# alt_rpd_schematic.net
KiCad netlist of a schematic drawn in EAGLE
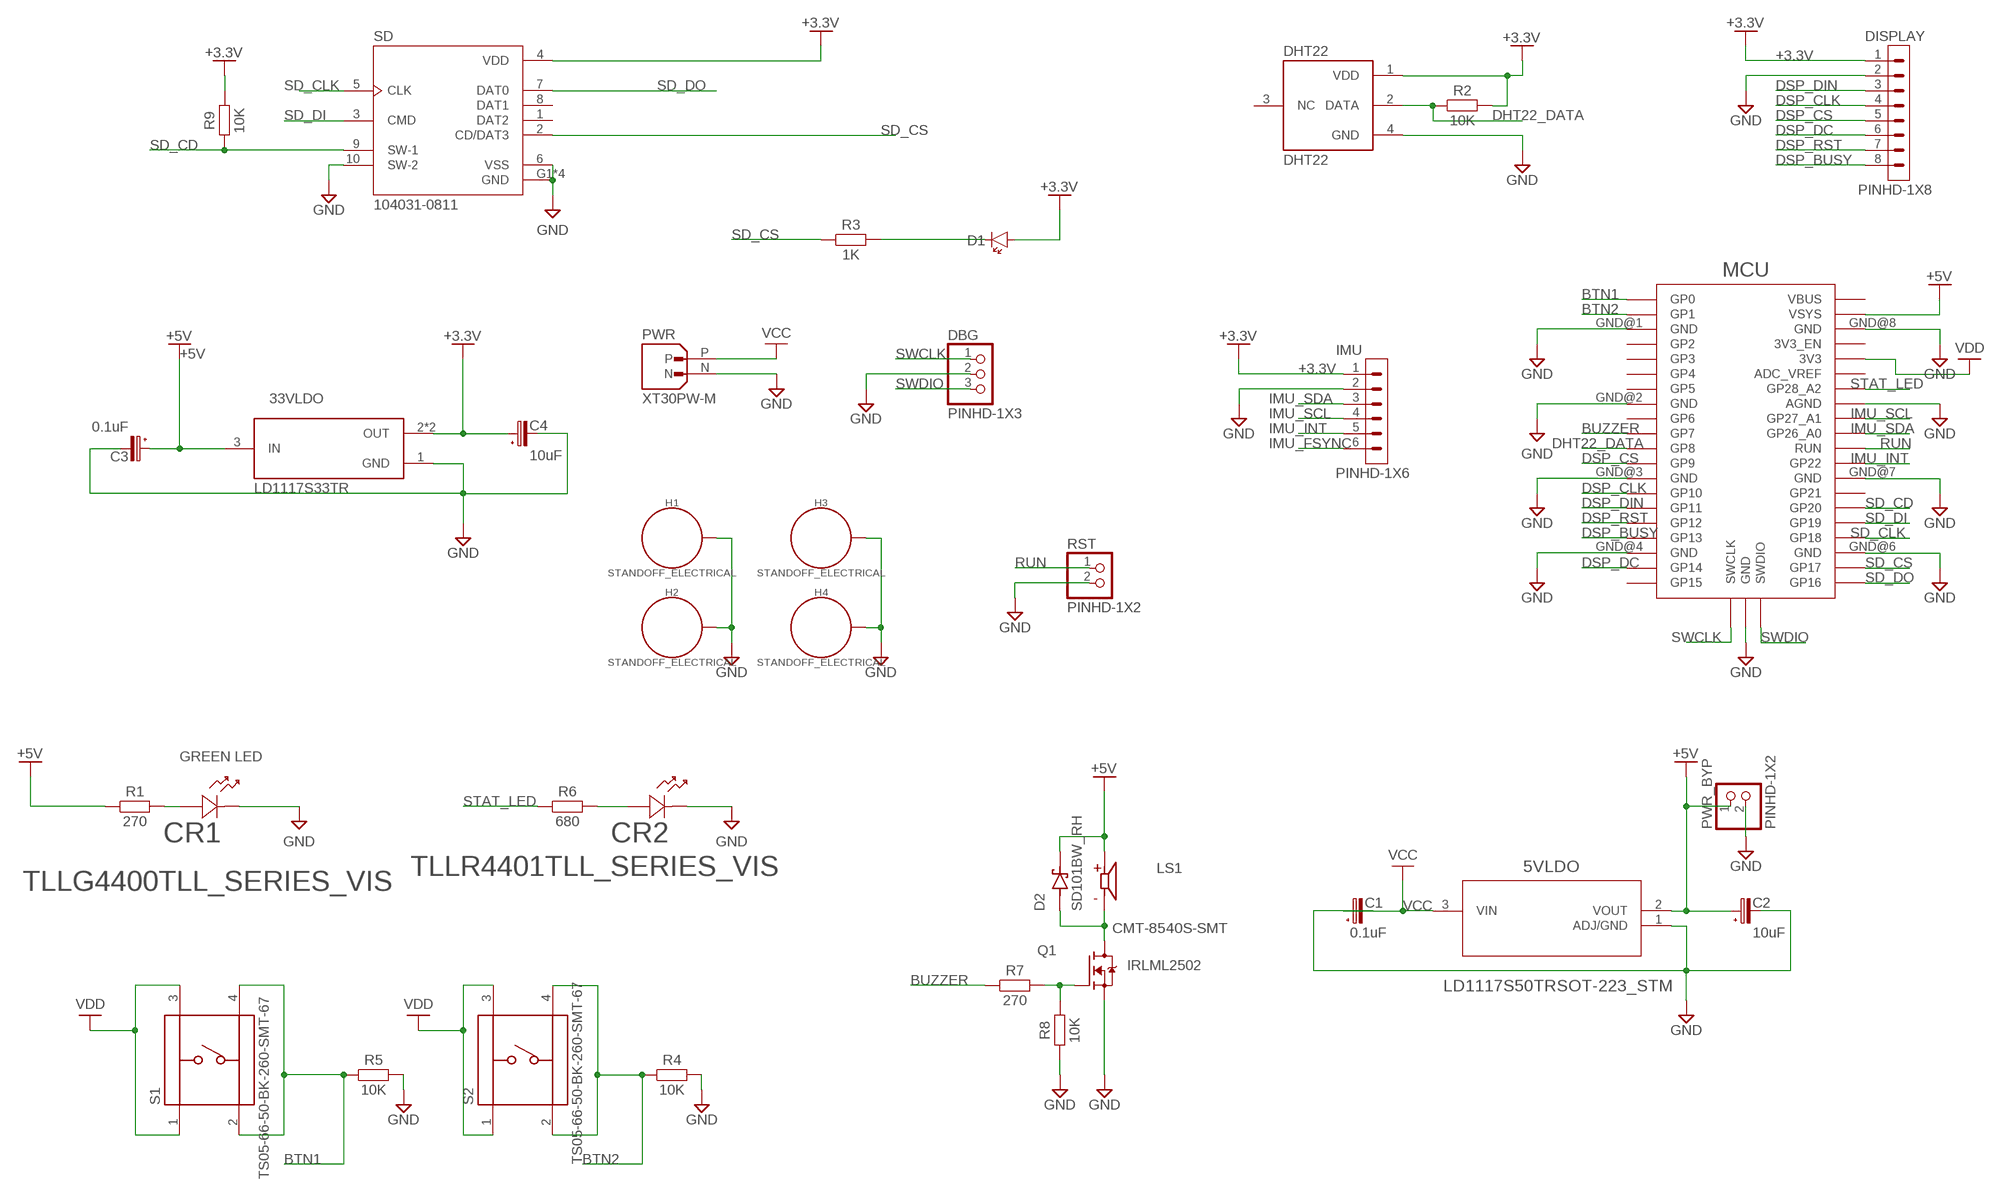
[diagram p0: schematic, sheet 1]

(export (version "E")
  (design (tool "Eeschema 10.0.6"))
  (components
    (comp (ref "5VLDO")
      (value "LD1117S50TRSOT-223_STM")
      (footprint "eagle-import:SOT-223_STM")
      (fields
        (field (name "MANUFACTURER_PART_NUMBER") "LD1117S50TR")
        (field (name "COPYRIGHT") "Copyright (C) 2026 Ultra Librarian. All rights reserved.")
      )
      (libsource (lib "eagle-import") (part "LD1117S50TRSOT-223_STM"))
    )
    (comp (ref "33VLDO")
      (value "LD1117S33TR")
      (footprint "eagle-import:SOT230P700X180-4N")
      (fields (field (name "MANUFACTURER") "ST Microelectronics"))
      (libsource (lib "eagle-import") (part "LD1117S33TR"))
    )
    (comp (ref "C1")
      (value "0.1uF")
      (footprint "eagle-import:CAPMP3216X180N")
      (libsource (lib "eagle-import") (part "C-POLTANTALUM-1206(3216-METRIC)_"))
    )
    (comp (ref "C2")
      (value "10uF")
      (footprint "eagle-import:CAPMP3216X180N")
      (libsource (lib "eagle-import") (part "C-POLTANTALUM-1206(3216-METRIC)_"))
    )
    (comp (ref "C3")
      (value "0.1uF")
      (footprint "eagle-import:CAPMP3216X180N")
      (libsource (lib "eagle-import") (part "C-POLTANTALUM-1206(3216-METRIC)_"))
    )
    (comp (ref "C4")
      (value "10uF")
      (footprint "eagle-import:CAPMP3216X180N")
      (libsource (lib "eagle-import") (part "C-POLTANTALUM-1206(3216-METRIC)_"))
    )
    (comp (ref "CR1")
      (value "TLLG4400TLL_SERIES_VIS")
      (footprint "eagle-import:TLL_SERIES_VIS")
      (description "GREEN LED")
      (fields
        (field (name "MANUFACTURER_PART_NUMBER") "TLLG4400")
        (field (name "COPYRIGHT") "Copyright (C) 2026 Ultra Librarian. All rights reserved.")
      )
      (libsource (lib "eagle-import") (part "TLLG4400TLL_SERIES_VIS"))
    )
    (comp (ref "CR2")
      (value "TLLR4401TLL_SERIES_VIS")
      (footprint "eagle-import:TLL_SERIES_VIS")
      (fields
        (field (name "MANUFACTURER_PART_NUMBER") "TLLR4401")
        (field (name "COPYRIGHT") "Copyright (C) 2026 Ultra Librarian. All rights reserved.")
      )
      (libsource (lib "eagle-import") (part "TLLR4401TLL_SERIES_VIS"))
    )
    (comp (ref "D1")
      (value "LED_RED")
      (footprint "eagle-import:LEDC2012X110N_FLAT-R")
      (libsource (lib "eagle-import") (part "CHIP-FLAT-R_0805"))
    )
    (comp (ref "D2")
      (value "SD101BW_RH")
      (footprint "eagle-import:DIO_SD101BW_RH")
      (fields (field (name "MF") "Taiwan Semiconductor") (field (name "MP") "BAT46GW RHG"))
      (libsource (lib "eagle-import") (part "SD101BW_RH"))
    )
    (comp (ref "DBG")
      (value "PINHD-1X3")
      (footprint "eagle-import:1X03")
      (libsource (lib "eagle-import") (part "PINHD-1X3"))
    )
    (comp (ref "DHT22")
      (value "DHT22")
      (footprint "eagle-import:XDCR_DHT22")
      (fields (field (name "MANUFACTURER") "Aosong Electronics") (field (name "CREATOR") "KARTHIK"))
      (libsource (lib "eagle-import") (part "DHT22"))
    )
    (comp (ref "DISPLAY")
      (value "PINHD-1X8")
      (footprint "eagle-import:1X08")
      (libsource (lib "eagle-import") (part "PINHD-1X8"))
    )
    (comp (ref "H1")
      (value "STANDOFF_ELECTRICAL")
      (footprint "eagle-import:STANDOFF-ELECTRICAL")
      (libsource (lib "eagle-import") (part "STANDOFF_ELECTRICAL"))
    )
    (comp (ref "H2")
      (value "STANDOFF_ELECTRICAL")
      (footprint "eagle-import:STANDOFF-ELECTRICAL")
      (libsource (lib "eagle-import") (part "STANDOFF_ELECTRICAL"))
    )
    (comp (ref "H3")
      (value "STANDOFF_ELECTRICAL")
      (footprint "eagle-import:STANDOFF-ELECTRICAL")
      (libsource (lib "eagle-import") (part "STANDOFF_ELECTRICAL"))
    )
    (comp (ref "H4")
      (value "STANDOFF_ELECTRICAL")
      (footprint "eagle-import:STANDOFF-ELECTRICAL")
      (libsource (lib "eagle-import") (part "STANDOFF_ELECTRICAL"))
    )
    (comp (ref "IMU")
      (value "PINHD-1X6")
      (footprint "eagle-import:1X06")
      (libsource (lib "eagle-import") (part "PINHD-1X6"))
    )
    (comp (ref "LS1")
      (value "CMT-8540S-SMT")
      (footprint "eagle-import:CUI_CMT-8540S-SMT")
      (fields (field (name "MF") "CUI"))
      (libsource (lib "eagle-import") (part "CMT-8540S-SMT"))
    )
    (comp (ref "MCU")
      (value "RPI_PICO_IG-SMD")
      (footprint "eagle-import:RPI_PICO")
      (libsource (lib "eagle-import") (part "RPI_PICO_IG-SMD"))
    )
    (comp (ref "PWR")
      (value "XT30PW-M")
      (footprint "eagle-import:AMASS_XT30PW-M")
      (fields (field (name "MANUFACTURER") "Amass"))
      (libsource (lib "eagle-import") (part "XT30PW-M"))
    )
    (comp (ref "PWR_BYP")
      (value "PINHD-1X2")
      (footprint "eagle-import:1X02")
      (libsource (lib "eagle-import") (part "PINHD-1X2"))
    )
    (comp (ref "Q1")
      (value "IRLML2502")
      (footprint "eagle-import:SOT95P237X112-3N")
      (fields (field (name "MANUFACTURER") "Infineon Technologies"))
      (libsource (lib "eagle-import") (part "IRLML2502"))
    )
    (comp (ref "R1")
      (value "270")
      (footprint "eagle-import:RESC3224X71")
      (libsource (lib "eagle-import") (part "RCHIP-1210(3225-METRIC)_"))
    )
    (comp (ref "R2")
      (value "10K")
      (footprint "eagle-import:RESC3216X70")
      (libsource (lib "eagle-import") (part "RCHIP-1206(3216-METRIC)_"))
    )
    (comp (ref "R3")
      (value "1K")
      (footprint "eagle-import:RESC3216X70")
      (libsource (lib "eagle-import") (part "RCHIP-1206(3216-METRIC)_"))
    )
    (comp (ref "R4")
      (value "10K")
      (footprint "eagle-import:RESC3216X70")
      (libsource (lib "eagle-import") (part "RCHIP-1206(3216-METRIC)_"))
    )
    (comp (ref "R5")
      (value "10K")
      (footprint "eagle-import:RESC3216X70")
      (libsource (lib "eagle-import") (part "RCHIP-1206(3216-METRIC)_"))
    )
    (comp (ref "R6")
      (value "680")
      (footprint "eagle-import:RESC3224X71")
      (libsource (lib "eagle-import") (part "RCHIP-1210(3225-METRIC)_"))
    )
    (comp (ref "R7")
      (value "270")
      (footprint "eagle-import:RESC3224X71")
      (libsource (lib "eagle-import") (part "RCHIP-1210(3225-METRIC)_"))
    )
    (comp (ref "R8")
      (value "10K")
      (footprint "eagle-import:RESC3216X70")
      (libsource (lib "eagle-import") (part "RCHIP-1206(3216-METRIC)_"))
    )
    (comp (ref "R9")
      (value "10K")
      (footprint "eagle-import:RESC3216X70")
      (libsource (lib "eagle-import") (part "RCHIP-1206(3216-METRIC)_"))
    )
    (comp (ref "RST")
      (value "PINHD-1X2")
      (footprint "eagle-import:1X02")
      (libsource (lib "eagle-import") (part "PINHD-1X2"))
    )
    (comp (ref "S1")
      (value "TS05-66-50-BK-260-SMT-67")
      (footprint "eagle-import:SW_TS05-66-50-BK-260-SMT-67")
      (fields (field (name "MANUFACTURER") "CUI Devices"))
      (libsource (lib "eagle-import") (part "TS05-66-50-BK-260-SMT-67"))
    )
    (comp (ref "S2")
      (value "TS05-66-50-BK-260-SMT-67")
      (footprint "eagle-import:SW_TS05-66-50-BK-260-SMT-67")
      (fields (field (name "MANUFACTURER") "CUI Devices"))
      (libsource (lib "eagle-import") (part "TS05-66-50-BK-260-SMT-67"))
    )
    (comp (ref "SD")
      (value "104031-0811")
      (footprint "eagle-import:MOLEX_104031-0811")
      (fields (field (name "MANUFACTURER") "Molex"))
      (libsource (lib "eagle-import") (part "104031-0811"))
    )
  )
  (nets
    (net (code "1") (name "+3.3V") (class "Default")
      (node (ref "33VLDO") (pin "2") (pinfunction "OUT_2") (pintype "output"))
      (node (ref "33VLDO") (pin "4") (pinfunction "OUT_4") (pintype "output"))
      (node (ref "C4") (pin "1") (pinfunction "+_1") (pintype "passive"))
      (node (ref "D1") (pin "A") (pinfunction "A_A") (pintype "passive"))
      (node (ref "DHT22") (pin "1") (pinfunction "VDD_1") (pintype "power_in"))
      (node (ref "DISPLAY") (pin "1") (pinfunction "1_1") (pintype "passive"))
      (node (ref "IMU") (pin "1") (pinfunction "1_1") (pintype "passive"))
      (node (ref "R2") (pin "2") (pinfunction "2_2") (pintype "passive"))
      (node (ref "R9") (pin "2") (pinfunction "2_2") (pintype "passive"))
      (node (ref "SD") (pin "4") (pinfunction "VDD_4") (pintype "power_in"))
    )
    (net (code "2") (name "+5V") (class "Default")
      (node (ref "33VLDO") (pin "3") (pinfunction "IN_3") (pintype "input"))
      (node (ref "5VLDO") (pin "2") (pinfunction "VOUT_2") (pintype "power_in"))
      (node (ref "C2") (pin "1") (pinfunction "+_1") (pintype "passive"))
      (node (ref "C3") (pin "1") (pinfunction "+_1") (pintype "passive"))
      (node (ref "D2") (pin "C") (pinfunction "K_C") (pintype "passive"))
      (node (ref "LS1") (pin "P") (pinfunction "P_P") (pintype "passive"))
      (node (ref "MCU") (pin "VSYS") (pinfunction "VSYS_VSYS") (pintype "bidirectional"))
      (node (ref "PWR_BYP") (pin "1") (pinfunction "1_1") (pintype "passive"))
      (node (ref "R1") (pin "1") (pinfunction "1_1") (pintype "passive"))
    )
    (net (code "3") (name "/BTN1") (class "Default")
      (node (ref "MCU") (pin "GP0") (pinfunction "GP0_GP0") (pintype "bidirectional"))
      (node (ref "R5") (pin "1") (pinfunction "1_1") (pintype "passive"))
      (node (ref "S1") (pin "2") (pinfunction "2_2") (pintype "passive"))
      (node (ref "S1") (pin "4") (pinfunction "4_4") (pintype "passive"))
    )
    (net (code "4") (name "/BTN2") (class "Default")
      (node (ref "MCU") (pin "GP1") (pinfunction "GP1_GP1") (pintype "bidirectional"))
      (node (ref "R4") (pin "1") (pinfunction "1_1") (pintype "passive"))
      (node (ref "S2") (pin "2") (pinfunction "2_2") (pintype "passive"))
      (node (ref "S2") (pin "4") (pinfunction "4_4") (pintype "passive"))
    )
    (net (code "5") (name "/BUZZER") (class "Default")
      (node (ref "MCU") (pin "GP7") (pinfunction "GP7_GP7") (pintype "bidirectional"))
      (node (ref "R7") (pin "1") (pinfunction "1_1") (pintype "passive"))
    )
    (net (code "6") (name "/DHT22_DATA") (class "Default")
      (node (ref "DHT22") (pin "2") (pinfunction "DATA_2") (pintype "bidirectional"))
      (node (ref "MCU") (pin "GP8") (pinfunction "GP8_GP8") (pintype "bidirectional"))
      (node (ref "R2") (pin "1") (pinfunction "1_1") (pintype "passive"))
    )
    (net (code "7") (name "/DSP_BUSY") (class "Default")
      (node (ref "DISPLAY") (pin "8") (pinfunction "8_8") (pintype "passive"))
      (node (ref "MCU") (pin "GP13") (pinfunction "GP13_GP13") (pintype "bidirectional"))
    )
    (net (code "8") (name "/DSP_CLK") (class "Default")
      (node (ref "DISPLAY") (pin "4") (pinfunction "4_4") (pintype "passive"))
      (node (ref "MCU") (pin "GP10") (pinfunction "GP10_GP10") (pintype "bidirectional"))
    )
    (net (code "9") (name "/DSP_CS") (class "Default")
      (node (ref "DISPLAY") (pin "5") (pinfunction "5_5") (pintype "passive"))
      (node (ref "MCU") (pin "GP9") (pinfunction "GP9_GP9") (pintype "bidirectional"))
    )
    (net (code "10") (name "/DSP_DC") (class "Default")
      (node (ref "DISPLAY") (pin "6") (pinfunction "6_6") (pintype "passive"))
      (node (ref "MCU") (pin "GP14") (pinfunction "GP14_GP14") (pintype "bidirectional"))
    )
    (net (code "11") (name "/DSP_DIN") (class "Default")
      (node (ref "DISPLAY") (pin "3") (pinfunction "3_3") (pintype "passive"))
      (node (ref "MCU") (pin "GP11") (pinfunction "GP11_GP11") (pintype "bidirectional"))
    )
    (net (code "12") (name "/DSP_RST") (class "Default")
      (node (ref "DISPLAY") (pin "7") (pinfunction "7_7") (pintype "passive"))
      (node (ref "MCU") (pin "GP12") (pinfunction "GP12_GP12") (pintype "bidirectional"))
    )
    (net (code "13") (name "/IMU_FSYNC") (class "Default")
      (node (ref "IMU") (pin "6") (pinfunction "6_6") (pintype "passive"))
    )
    (net (code "14") (name "/IMU_INT") (class "Default")
      (node (ref "IMU") (pin "5") (pinfunction "5_5") (pintype "passive"))
      (node (ref "MCU") (pin "GP22") (pinfunction "GP22_GP22") (pintype "bidirectional"))
    )
    (net (code "15") (name "/IMU_SCL") (class "Default")
      (node (ref "IMU") (pin "4") (pinfunction "4_4") (pintype "passive"))
      (node (ref "MCU") (pin "GP27_A1") (pinfunction "GP27_A1_GP27_A1") (pintype "bidirectional"))
    )
    (net (code "16") (name "/IMU_SDA") (class "Default")
      (node (ref "IMU") (pin "3") (pinfunction "3_3") (pintype "passive"))
      (node (ref "MCU") (pin "GP26_A0") (pinfunction "GP26_A0_GP26_A0") (pintype "bidirectional"))
    )
    (net (code "17") (name "/RUN") (class "Default")
      (node (ref "MCU") (pin "RUN") (pinfunction "RUN_RUN") (pintype "bidirectional"))
      (node (ref "RST") (pin "1") (pinfunction "1_1") (pintype "passive"))
    )
    (net (code "18") (name "/SD_CD") (class "Default")
      (node (ref "MCU") (pin "GP20") (pinfunction "GP20_GP20") (pintype "bidirectional"))
      (node (ref "R9") (pin "1") (pinfunction "1_1") (pintype "passive"))
      (node (ref "SD") (pin "9") (pinfunction "SW-1_9") (pintype "passive"))
    )
    (net (code "19") (name "/SD_CLK") (class "Default")
      (node (ref "MCU") (pin "GP18") (pinfunction "GP18_GP18") (pintype "bidirectional"))
      (node (ref "SD") (pin "5") (pinfunction "CLK_5") (pintype "input"))
    )
    (net (code "20") (name "/SD_CS") (class "Default")
      (node (ref "MCU") (pin "GP17") (pinfunction "GP17_GP17") (pintype "bidirectional"))
      (node (ref "R3") (pin "1") (pinfunction "1_1") (pintype "passive"))
      (node (ref "SD") (pin "2") (pinfunction "CD/DAT3_2") (pintype "bidirectional"))
    )
    (net (code "21") (name "/SD_DI") (class "Default")
      (node (ref "MCU") (pin "GP19") (pinfunction "GP19_GP19") (pintype "bidirectional"))
      (node (ref "SD") (pin "3") (pinfunction "CMD_3") (pintype "bidirectional"))
    )
    (net (code "22") (name "/SD_DO") (class "Default")
      (node (ref "MCU") (pin "GP16") (pinfunction "GP16_GP16") (pintype "bidirectional"))
      (node (ref "SD") (pin "7") (pinfunction "DAT0_7") (pintype "bidirectional"))
    )
    (net (code "23") (name "/STAT_LED") (class "Default")
      (node (ref "MCU") (pin "GP28_A2") (pinfunction "GP28_A2_GP28_A2") (pintype "bidirectional"))
      (node (ref "R6") (pin "1") (pinfunction "1_1") (pintype "passive"))
    )
    (net (code "24") (name "/SWCLK") (class "Default")
      (node (ref "DBG") (pin "1") (pinfunction "1_1") (pintype "passive"))
      (node (ref "MCU") (pin "SWCLK") (pinfunction "SWCLK_SWCLK") (pintype "bidirectional"))
    )
    (net (code "25") (name "/SWDIO") (class "Default")
      (node (ref "DBG") (pin "3") (pinfunction "3_3") (pintype "passive"))
      (node (ref "MCU") (pin "SWDIO") (pinfunction "SWDIO_SWDIO") (pintype "bidirectional"))
    )
    (net (code "26") (name "GND") (class "Default")
      (node (ref "33VLDO") (pin "1") (pinfunction "GND_1") (pintype "power_in"))
      (node (ref "5VLDO") (pin "1") (pinfunction "ADJ/GND_1") (pintype "passive"))
      (node (ref "C1") (pin "2") (pinfunction "-_2") (pintype "passive"))
      (node (ref "C2") (pin "2") (pinfunction "-_2") (pintype "passive"))
      (node (ref "C3") (pin "2") (pinfunction "-_2") (pintype "passive"))
      (node (ref "C4") (pin "2") (pinfunction "-_2") (pintype "passive"))
      (node (ref "CR1") (pin "1") (pinfunction "1_1") (pintype "passive"))
      (node (ref "CR2") (pin "1") (pinfunction "1_1") (pintype "passive"))
      (node (ref "DBG") (pin "2") (pinfunction "2_2") (pintype "passive"))
      (node (ref "DHT22") (pin "4") (pinfunction "GND_4") (pintype "power_in"))
      (node (ref "DISPLAY") (pin "2") (pinfunction "2_2") (pintype "passive"))
      (node (ref "H1") (pin "P1") (pinfunction "P$1_P1") (pintype "bidirectional"))
      (node (ref "H2") (pin "P1") (pinfunction "P$1_P1") (pintype "bidirectional"))
      (node (ref "H3") (pin "P1") (pinfunction "P$1_P1") (pintype "bidirectional"))
      (node (ref "H4") (pin "P1") (pinfunction "P$1_P1") (pintype "bidirectional"))
      (node (ref "IMU") (pin "2") (pinfunction "2_2") (pintype "passive"))
      (node (ref "MCU") (pin "AGND") (pinfunction "AGND_AGND") (pintype "bidirectional"))
      (node (ref "MCU") (pin "GND@1") (pinfunction "GND_GND@1") (pintype "bidirectional"))
      (node (ref "MCU") (pin "GND@2") (pinfunction "GND_GND@2") (pintype "bidirectional"))
      (node (ref "MCU") (pin "GND@3") (pinfunction "GND_GND@3") (pintype "bidirectional"))
      (node (ref "MCU") (pin "GND@4") (pinfunction "GND_GND@4") (pintype "bidirectional"))
      (node (ref "MCU") (pin "GND@5") (pinfunction "GND_GND@5") (pintype "bidirectional"))
      (node (ref "MCU") (pin "GND@6") (pinfunction "GND_GND@6") (pintype "bidirectional"))
      (node (ref "MCU") (pin "GND@7") (pinfunction "GND_GND@7") (pintype "bidirectional"))
      (node (ref "MCU") (pin "GND@8") (pinfunction "GND_GND@8") (pintype "bidirectional"))
      (node (ref "PWR") (pin "N") (pinfunction "N_N") (pintype "power_in"))
      (node (ref "PWR_BYP") (pin "2") (pinfunction "2_2") (pintype "passive"))
      (node (ref "Q1") (pin "2") (pinfunction "S_2") (pintype "passive"))
      (node (ref "R4") (pin "2") (pinfunction "2_2") (pintype "passive"))
      (node (ref "R5") (pin "2") (pinfunction "2_2") (pintype "passive"))
      (node (ref "R8") (pin "1") (pinfunction "1_1") (pintype "passive"))
      (node (ref "RST") (pin "2") (pinfunction "2_2") (pintype "passive"))
      (node (ref "SD") (pin "10") (pinfunction "SW-2_10") (pintype "passive"))
      (node (ref "SD") (pin "6") (pinfunction "VSS_6") (pintype "power_in"))
      (node (ref "SD") (pin "G1") (pinfunction "GND_G1") (pintype "power_in"))
      (node (ref "SD") (pin "G2") (pinfunction "GND_G2") (pintype "power_in"))
      (node (ref "SD") (pin "G3") (pinfunction "GND_G3") (pintype "power_in"))
      (node (ref "SD") (pin "G4") (pinfunction "GND_G4") (pintype "power_in"))
    )
    (net (code "27") (name "Net-(CR1-Pad2)") (class "Default")
      (node (ref "CR1") (pin "2") (pinfunction "2_2") (pintype "passive"))
      (node (ref "R1") (pin "2") (pinfunction "2_2") (pintype "passive"))
    )
    (net (code "28") (name "Net-(CR2-Pad2)") (class "Default")
      (node (ref "CR2") (pin "2") (pinfunction "2_2") (pintype "passive"))
      (node (ref "R6") (pin "2") (pinfunction "2_2") (pintype "passive"))
    )
    (net (code "29") (name "Net-(D1-PadC)") (class "Default")
      (node (ref "D1") (pin "C") (pinfunction "C_C") (pintype "passive"))
      (node (ref "R3") (pin "2") (pinfunction "2_2") (pintype "passive"))
    )
    (net (code "30") (name "Net-(Q1-D)") (class "Default")
      (node (ref "D2") (pin "A") (pinfunction "A_A") (pintype "passive"))
      (node (ref "LS1") (pin "N") (pinfunction "N_N") (pintype "passive"))
      (node (ref "Q1") (pin "3") (pinfunction "D_3") (pintype "passive"))
    )
    (net (code "31") (name "Net-(Q1-G)") (class "Default")
      (node (ref "Q1") (pin "1") (pinfunction "G_1") (pintype "passive"))
      (node (ref "R7") (pin "2") (pinfunction "2_2") (pintype "passive"))
      (node (ref "R8") (pin "2") (pinfunction "2_2") (pintype "passive"))
    )
    (net (code "32") (name "VCC") (class "Default")
      (node (ref "5VLDO") (pin "3") (pinfunction "VIN_3") (pintype "power_in"))
      (node (ref "C1") (pin "1") (pinfunction "+_1") (pintype "passive"))
      (node (ref "PWR") (pin "P") (pinfunction "P_P") (pintype "power_in"))
    )
    (net (code "33") (name "VDD") (class "Default")
      (node (ref "MCU") (pin "3V3") (pinfunction "3V3_3V3") (pintype "bidirectional"))
      (node (ref "S1") (pin "1") (pinfunction "1_1") (pintype "passive"))
      (node (ref "S1") (pin "3") (pinfunction "3_3") (pintype "passive"))
      (node (ref "S2") (pin "1") (pinfunction "1_1") (pintype "passive"))
      (node (ref "S2") (pin "3") (pinfunction "3_3") (pintype "passive"))
    )
    (net (code "34") (name "unconnected-(DHT22-NC-Pad3)") (class "Default")
      (node (ref "DHT22") (pin "3") (pinfunction "NC_3") (pintype "no_connect"))
    )
    (net (code "35") (name "unconnected-(MCU-Pad3V3_EN)") (class "Default")
      (node (ref "MCU") (pin "3V3_EN") (pinfunction "3V3_EN_3V3_EN") (pintype "bidirectional"))
    )
    (net (code "36") (name "unconnected-(MCU-PadADC_VREF)") (class "Default")
      (node (ref "MCU") (pin "ADC_VREF") (pinfunction "ADC_VREF_ADC_VREF") (pintype "bidirectional"))
    )
    (net (code "37") (name "unconnected-(MCU-PadGP2)") (class "Default")
      (node (ref "MCU") (pin "GP2") (pinfunction "GP2_GP2") (pintype "bidirectional"))
    )
    (net (code "38") (name "unconnected-(MCU-PadGP3)") (class "Default")
      (node (ref "MCU") (pin "GP3") (pinfunction "GP3_GP3") (pintype "bidirectional"))
    )
    (net (code "39") (name "unconnected-(MCU-PadGP4)") (class "Default")
      (node (ref "MCU") (pin "GP4") (pinfunction "GP4_GP4") (pintype "bidirectional"))
    )
    (net (code "40") (name "unconnected-(MCU-PadGP5)") (class "Default")
      (node (ref "MCU") (pin "GP5") (pinfunction "GP5_GP5") (pintype "bidirectional"))
    )
    (net (code "41") (name "unconnected-(MCU-PadGP6)") (class "Default")
      (node (ref "MCU") (pin "GP6") (pinfunction "GP6_GP6") (pintype "bidirectional"))
    )
    (net (code "42") (name "unconnected-(MCU-PadGP15)") (class "Default")
      (node (ref "MCU") (pin "GP15") (pinfunction "GP15_GP15") (pintype "bidirectional"))
    )
    (net (code "43") (name "unconnected-(MCU-PadGP21)") (class "Default")
      (node (ref "MCU") (pin "GP21") (pinfunction "GP21_GP21") (pintype "bidirectional"))
    )
    (net (code "44") (name "unconnected-(MCU-PadVBUS)") (class "Default")
      (node (ref "MCU") (pin "VBUS") (pinfunction "VBUS_VBUS") (pintype "bidirectional"))
    )
    (net (code "45") (name "unconnected-(SD-DAT1-Pad8)") (class "Default")
      (node (ref "SD") (pin "8") (pinfunction "DAT1_8") (pintype "bidirectional"))
    )
    (net (code "46") (name "unconnected-(SD-DAT2-Pad1)") (class "Default")
      (node (ref "SD") (pin "1") (pinfunction "DAT2_1") (pintype "bidirectional"))
    )
  )
)
